# Adafruit_EZ-SFX_with_Headphone.net
KiCad netlist of a schematic drawn in EAGLE
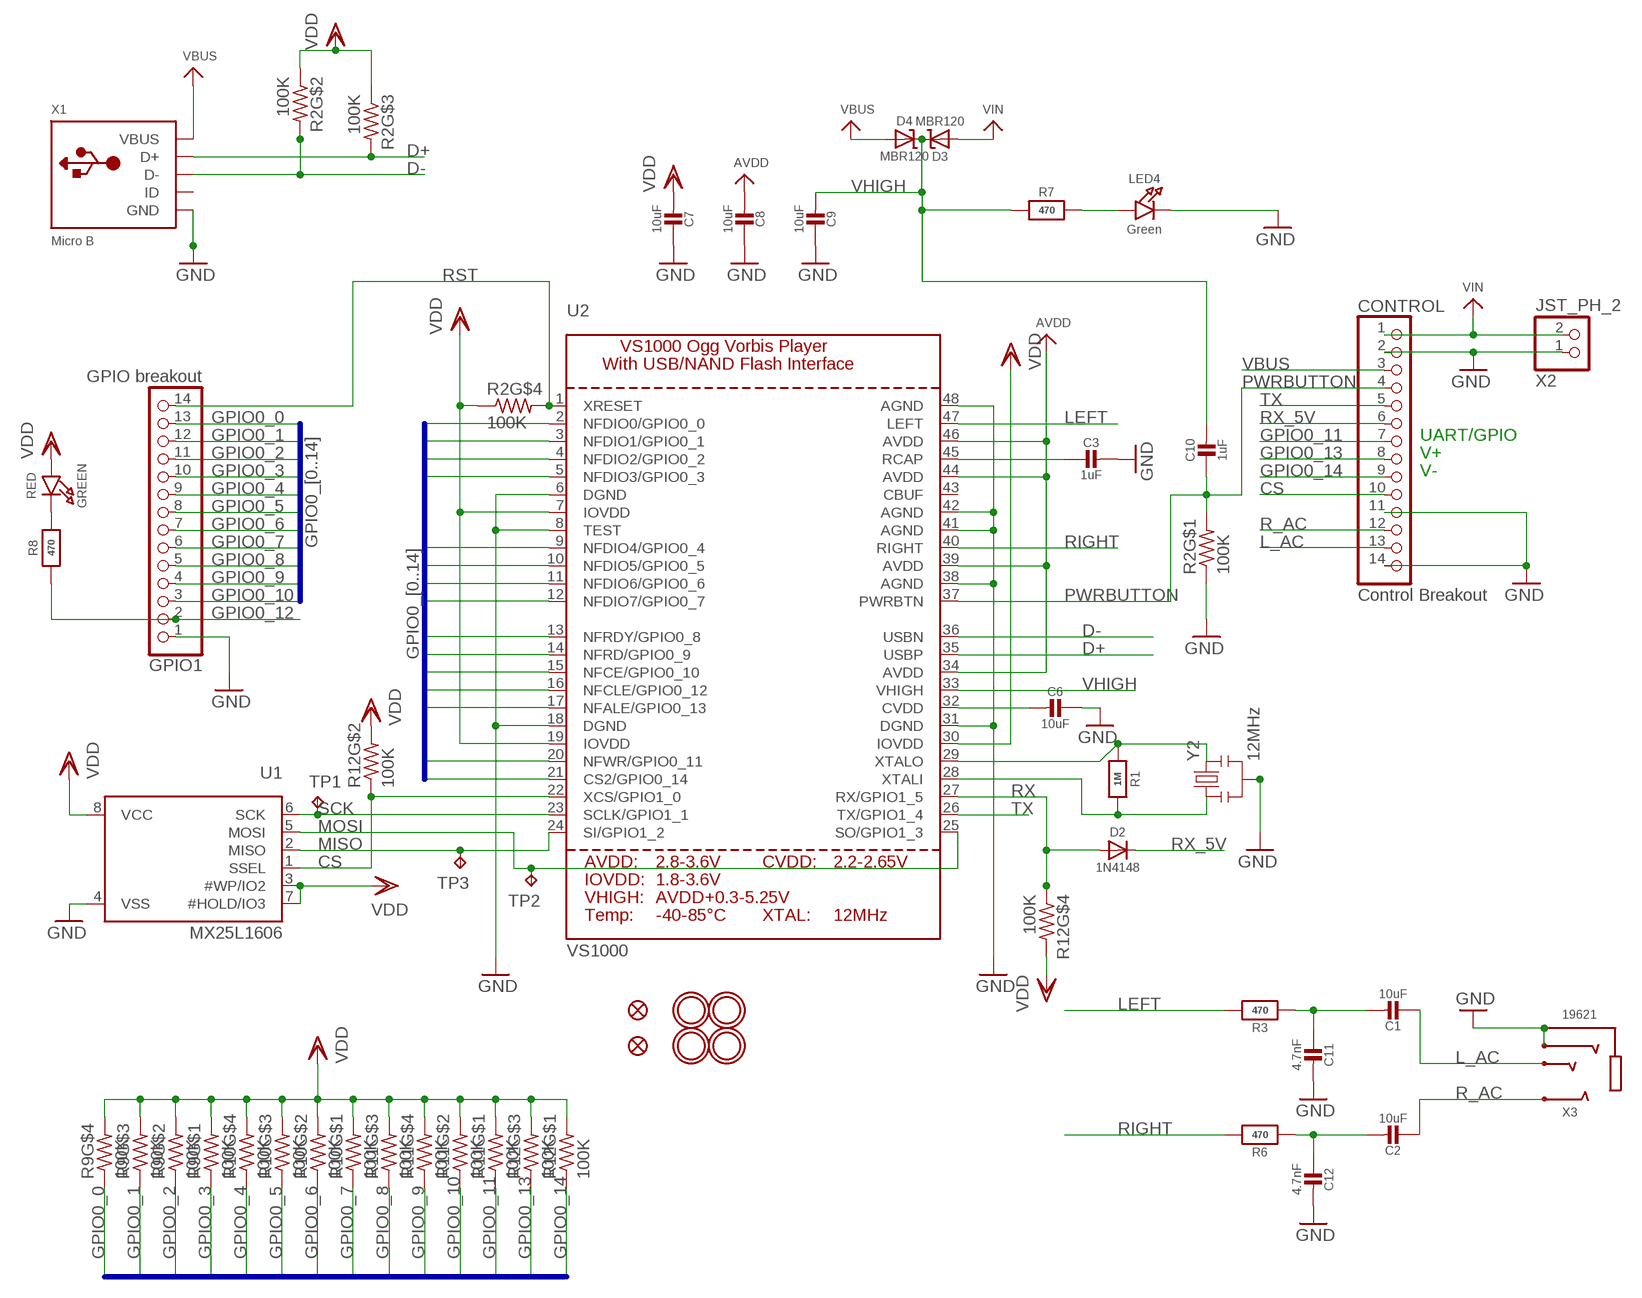
[diagram p0: schematic, sheet 1]

(export (version "E")
  (design (tool "Eeschema 10.0.6"))
  (components
    (comp (ref "C1")
      (value "10uF")
      (footprint "eagle-import:0805-NO")
      (libsource (lib "eagle-import") (part "CAP_CERAMIC0805-NOOUTLINE"))
    )
    (comp (ref "C2")
      (value "10uF")
      (footprint "eagle-import:0805-NO")
      (libsource (lib "eagle-import") (part "CAP_CERAMIC0805-NOOUTLINE"))
    )
    (comp (ref "C3")
      (value "1uF")
      (footprint "eagle-import:0805-NO")
      (libsource (lib "eagle-import") (part "CAP_CERAMIC0805-NOOUTLINE"))
    )
    (comp (ref "C6")
      (value "10uF")
      (footprint "eagle-import:0805_10MGAP")
      (libsource (lib "eagle-import") (part "CAP_CERAMIC0805_10MGAP"))
    )
    (comp (ref "C7")
      (value "10uF")
      (footprint "eagle-import:0805_10MGAP")
      (libsource (lib "eagle-import") (part "CAP_CERAMIC0805_10MGAP"))
    )
    (comp (ref "C8")
      (value "10uF")
      (footprint "eagle-import:0805-NO")
      (libsource (lib "eagle-import") (part "CAP_CERAMIC0805-NOOUTLINE"))
    )
    (comp (ref "C9")
      (value "10uF")
      (footprint "eagle-import:0805-NO")
      (libsource (lib "eagle-import") (part "CAP_CERAMIC0805-NOOUTLINE"))
    )
    (comp (ref "C10")
      (value "1uF")
      (footprint "eagle-import:0805-NO")
      (libsource (lib "eagle-import") (part "CAP_CERAMIC0805-NOOUTLINE"))
    )
    (comp (ref "C11")
      (value "4.7nF")
      (footprint "eagle-import:0805-NO")
      (libsource (lib "eagle-import") (part "CAP_CERAMIC0805-NOOUTLINE"))
    )
    (comp (ref "C12")
      (value "4.7nF")
      (footprint "eagle-import:0805-NO")
      (libsource (lib "eagle-import") (part "CAP_CERAMIC0805-NOOUTLINE"))
    )
    (comp (ref "CONTROL")
      (value "Control Breakout")
      (footprint "eagle-import:1X14-CB")
      (libsource (lib "eagle-import") (part "PINHD-1X14-CB"))
    )
    (comp (ref "D2")
      (value "1N4148")
      (footprint "eagle-import:SOD-323")
      (libsource (lib "eagle-import") (part "DIODESOD-323"))
    )
    (comp (ref "D3")
      (value "MBR120")
      (footprint "eagle-import:SOD-123")
      (libsource (lib "eagle-import") (part "DIODE-SCHOTTKYSOD-123"))
    )
    (comp (ref "D4")
      (value "MBR120")
      (footprint "eagle-import:SOD-123")
      (libsource (lib "eagle-import") (part "DIODE-SCHOTTKYSOD-123"))
    )
    (comp (ref "FID1")
      (value "FIDUCIAL\"\"")
      (footprint "eagle-import:FIDUCIAL_1MM")
      (libsource (lib "eagle-import") (part "FIDUCIAL{dblquote}{dblquote}"))
    )
    (comp (ref "FID2")
      (value "FIDUCIAL\"\"")
      (footprint "eagle-import:FIDUCIAL_1MM")
      (libsource (lib "eagle-import") (part "FIDUCIAL{dblquote}{dblquote}"))
    )
    (comp (ref "GPIO1")
      (value "GPIO breakout")
      (footprint "eagle-import:1X14-CB")
      (libsource (lib "eagle-import") (part "PINHD-1X14-CB"))
    )
    (comp (ref "GREEN")
      (value "RED")
      (footprint "eagle-import:CHIPLED_0805_NOOUTLINE")
      (libsource (lib "eagle-import") (part "LED0805_NOOUTLINE"))
    )
    (comp (ref "LED4")
      (value "Green")
      (footprint "eagle-import:CHIPLED_0805_NOOUTLINE")
      (libsource (lib "eagle-import") (part "LED0805_NOOUTLINE"))
    )
    (comp (ref "R1")
      (value "1M")
      (footprint "eagle-import:0805-NO")
      (libsource (lib "eagle-import") (part "RESISTOR0805_NOOUTLINE"))
    )
    (comp (ref "R2")
      (value "100K")
      (footprint "eagle-import:RESPACK_4X0603")
      (libsource (lib "eagle-import") (part "RESISTOR_4PACK_US"))
    )
    (comp (ref "R3")
      (value "470")
      (footprint "eagle-import:0805-NO")
      (libsource (lib "eagle-import") (part "RESISTOR0805_NOOUTLINE"))
    )
    (comp (ref "R6")
      (value "470")
      (footprint "eagle-import:0805-NO")
      (libsource (lib "eagle-import") (part "RESISTOR0805_NOOUTLINE"))
    )
    (comp (ref "R7")
      (value "470")
      (footprint "eagle-import:0805-NO")
      (libsource (lib "eagle-import") (part "RESISTOR0805_NOOUTLINE"))
    )
    (comp (ref "R8")
      (value "470")
      (footprint "eagle-import:0805-NO")
      (libsource (lib "eagle-import") (part "RESISTOR0805_NOOUTLINE"))
    )
    (comp (ref "R9")
      (value "100K")
      (footprint "eagle-import:RESPACK_4X0603")
      (libsource (lib "eagle-import") (part "RESISTOR_4PACK_US"))
    )
    (comp (ref "R10")
      (value "100K")
      (footprint "eagle-import:RESPACK_4X0603")
      (libsource (lib "eagle-import") (part "RESISTOR_4PACK_US"))
    )
    (comp (ref "R11")
      (value "100K")
      (footprint "eagle-import:RESPACK_4X0603")
      (libsource (lib "eagle-import") (part "RESISTOR_4PACK_US"))
    )
    (comp (ref "R12")
      (value "100K")
      (footprint "eagle-import:RESPACK_4X0603")
      (libsource (lib "eagle-import") (part "RESISTOR_4PACK_US"))
    )
    (comp (ref "TP1")
      (value "TPB1,27")
      (footprint "eagle-import:B1,27")
      (libsource (lib "eagle-import") (part "TPB1,27"))
    )
    (comp (ref "TP2")
      (value "TPB1,27")
      (footprint "eagle-import:B1,27")
      (libsource (lib "eagle-import") (part "TPB1,27"))
    )
    (comp (ref "TP3")
      (value "TPB1,27")
      (footprint "eagle-import:B1,27")
      (libsource (lib "eagle-import") (part "TPB1,27"))
    )
    (comp (ref "U$5")
      (value "MOUNTINGHOLE2.5")
      (footprint "eagle-import:MOUNTINGHOLE_2.5_PLATED")
      (libsource (lib "eagle-import") (part "MOUNTINGHOLE2.5"))
    )
    (comp (ref "U$6")
      (value "MOUNTINGHOLE2.5")
      (footprint "eagle-import:MOUNTINGHOLE_2.5_PLATED")
      (libsource (lib "eagle-import") (part "MOUNTINGHOLE2.5"))
    )
    (comp (ref "U$7")
      (value "MOUNTINGHOLE2.5")
      (footprint "eagle-import:MOUNTINGHOLE_2.5_PLATED")
      (libsource (lib "eagle-import") (part "MOUNTINGHOLE2.5"))
    )
    (comp (ref "U$8")
      (value "MOUNTINGHOLE2.5")
      (footprint "eagle-import:MOUNTINGHOLE_2.5_PLATED")
      (libsource (lib "eagle-import") (part "MOUNTINGHOLE2.5"))
    )
    (comp (ref "U1")
      (value "MX25L1606")
      (footprint "eagle-import:SOIC8_208MIL")
      (libsource (lib "eagle-import") (part "SPIFLASH_SOIC8208MIL"))
    )
    (comp (ref "U2")
      (value "VS1000")
      (footprint "eagle-import:LQFP48")
      (libsource (lib "eagle-import") (part "VS1000"))
    )
    (comp (ref "X1")
      (value "Micro B")
      (footprint "eagle-import:4UCONN_20329")
      (libsource (lib "eagle-import") (part "USBMICRO_20329"))
    )
    (comp (ref "X2")
      (value "JST_PH_2")
      (footprint "eagle-import:JSTPH2")
      (libsource (lib "eagle-import") (part "CON_JST_PH_2PIN"))
    )
    (comp (ref "X3")
      (value "19621")
      (footprint "eagle-import:4UCONN_18510")
      (libsource (lib "eagle-import") (part "AUDIO_3.5MMJACK_4POL"))
    )
    (comp (ref "Y2")
      (value "12MHz")
      (footprint "eagle-import:RESONATOR-SMD")
      (libsource (lib "eagle-import") (part "RESONATORSMD"))
    )
  )
  (nets
    (net (code "1") (name "/CS") (class "Default")
      (node (ref "CONTROL") (pin "10") (pinfunction "10_10") (pintype "passive"))
      (node (ref "R12") (pin "2") (pinfunction "1_2") (pintype "passive"))
      (node (ref "U1") (pin "1") (pinfunction "SSEL_1") (pintype "bidirectional"))
      (node (ref "U2") (pin "22") (pinfunction "XCS/GPIO1_0_22") (pintype "bidirectional"))
    )
    (net (code "2") (name "/D+") (class "Default")
      (node (ref "R2") (pin "6") (pinfunction "2_6") (pintype "passive"))
      (node (ref "U2") (pin "35") (pinfunction "USBP_35") (pintype "bidirectional"))
      (node (ref "X1") (pin "D+") (pinfunction "D+_D+") (pintype "bidirectional"))
    )
    (net (code "3") (name "/D-") (class "Default")
      (node (ref "R2") (pin "7") (pinfunction "2_7") (pintype "passive"))
      (node (ref "U2") (pin "36") (pinfunction "USBN_36") (pintype "bidirectional"))
      (node (ref "X1") (pin "D-") (pinfunction "D-_D-") (pintype "bidirectional"))
    )
    (net (code "4") (name "/GPIO0_0") (class "Default")
      (node (ref "GPIO1") (pin "13") (pinfunction "13_13") (pintype "passive"))
      (node (ref "R9") (pin "4") (pinfunction "1_4") (pintype "passive"))
      (node (ref "U2") (pin "2") (pinfunction "NFDIO0/GPIO0_0_2") (pintype "bidirectional"))
    )
    (net (code "5") (name "/GPIO0_1") (class "Default")
      (node (ref "GPIO1") (pin "12") (pinfunction "12_12") (pintype "passive"))
      (node (ref "R9") (pin "3") (pinfunction "1_3") (pintype "passive"))
      (node (ref "U2") (pin "3") (pinfunction "NFDIO1/GPIO0_1_3") (pintype "bidirectional"))
    )
    (net (code "6") (name "/GPIO0_2") (class "Default")
      (node (ref "GPIO1") (pin "11") (pinfunction "11_11") (pintype "passive"))
      (node (ref "R9") (pin "2") (pinfunction "1_2") (pintype "passive"))
      (node (ref "U2") (pin "4") (pinfunction "NFDIO2/GPIO0_2_4") (pintype "bidirectional"))
    )
    (net (code "7") (name "/GPIO0_3") (class "Default")
      (node (ref "GPIO1") (pin "10") (pinfunction "10_10") (pintype "passive"))
      (node (ref "R9") (pin "1") (pinfunction "1_1") (pintype "passive"))
      (node (ref "U2") (pin "5") (pinfunction "NFDIO3/GPIO0_3_5") (pintype "bidirectional"))
    )
    (net (code "8") (name "/GPIO0_4") (class "Default")
      (node (ref "GPIO1") (pin "9") (pinfunction "9_9") (pintype "passive"))
      (node (ref "R10") (pin "4") (pinfunction "1_4") (pintype "passive"))
      (node (ref "U2") (pin "9") (pinfunction "NFDIO4/GPIO0_4_9") (pintype "bidirectional"))
    )
    (net (code "9") (name "/GPIO0_5") (class "Default")
      (node (ref "GPIO1") (pin "8") (pinfunction "8_8") (pintype "passive"))
      (node (ref "R10") (pin "3") (pinfunction "1_3") (pintype "passive"))
      (node (ref "U2") (pin "10") (pinfunction "NFDIO5/GPIO0_5_10") (pintype "bidirectional"))
    )
    (net (code "10") (name "/GPIO0_6") (class "Default")
      (node (ref "GPIO1") (pin "7") (pinfunction "7_7") (pintype "passive"))
      (node (ref "R10") (pin "2") (pinfunction "1_2") (pintype "passive"))
      (node (ref "U2") (pin "11") (pinfunction "NFDIO6/GPIO0_6_11") (pintype "bidirectional"))
    )
    (net (code "11") (name "/GPIO0_7") (class "Default")
      (node (ref "GPIO1") (pin "6") (pinfunction "6_6") (pintype "passive"))
      (node (ref "R10") (pin "1") (pinfunction "1_1") (pintype "passive"))
      (node (ref "U2") (pin "12") (pinfunction "NFDIO7/GPIO0_7_12") (pintype "bidirectional"))
    )
    (net (code "12") (name "/GPIO0_8") (class "Default")
      (node (ref "GPIO1") (pin "5") (pinfunction "5_5") (pintype "passive"))
      (node (ref "R11") (pin "3") (pinfunction "1_3") (pintype "passive"))
      (node (ref "U2") (pin "13") (pinfunction "NFRDY/GPIO0_8_13") (pintype "bidirectional"))
    )
    (net (code "13") (name "/GPIO0_9") (class "Default")
      (node (ref "GPIO1") (pin "4") (pinfunction "4_4") (pintype "passive"))
      (node (ref "R11") (pin "4") (pinfunction "1_4") (pintype "passive"))
      (node (ref "U2") (pin "14") (pinfunction "NFRD/GPIO0_9_14") (pintype "bidirectional"))
    )
    (net (code "14") (name "/GPIO0_10") (class "Default")
      (node (ref "GPIO1") (pin "3") (pinfunction "3_3") (pintype "passive"))
      (node (ref "R11") (pin "2") (pinfunction "1_2") (pintype "passive"))
      (node (ref "U2") (pin "15") (pinfunction "NFCE/GPIO0_10_15") (pintype "bidirectional"))
    )
    (net (code "15") (name "/GPIO0_11") (class "Default")
      (node (ref "CONTROL") (pin "7") (pinfunction "7_7") (pintype "passive"))
      (node (ref "R11") (pin "1") (pinfunction "1_1") (pintype "passive"))
      (node (ref "U2") (pin "20") (pinfunction "NFWR/GPIO0_11_20") (pintype "bidirectional"))
    )
    (net (code "16") (name "/GPIO0_12") (class "Default")
      (node (ref "GPIO1") (pin "2") (pinfunction "2_2") (pintype "passive"))
      (node (ref "R8") (pin "2") (pinfunction "2_2") (pintype "passive"))
      (node (ref "U2") (pin "16") (pinfunction "NFCLE/GPIO0_12_16") (pintype "bidirectional"))
    )
    (net (code "17") (name "/GPIO0_13") (class "Default")
      (node (ref "CONTROL") (pin "8") (pinfunction "8_8") (pintype "passive"))
      (node (ref "R12") (pin "3") (pinfunction "1_3") (pintype "passive"))
      (node (ref "U2") (pin "17") (pinfunction "NFALE/GPIO0_13_17") (pintype "bidirectional"))
    )
    (net (code "18") (name "/GPIO0_14") (class "Default")
      (node (ref "CONTROL") (pin "9") (pinfunction "9_9") (pintype "passive"))
      (node (ref "R12") (pin "1") (pinfunction "1_1") (pintype "passive"))
      (node (ref "U2") (pin "21") (pinfunction "CS2/GPIO0_14_21") (pintype "bidirectional"))
    )
    (net (code "20") (name "/LEFT") (class "Default")
      (node (ref "R3") (pin "1") (pinfunction "1_1") (pintype "passive"))
      (node (ref "U2") (pin "47") (pinfunction "LEFT_47") (pintype "bidirectional"))
    )
    (net (code "21") (name "/L_AC") (class "Default")
      (node (ref "C1") (pin "1") (pinfunction "1_1") (pintype "passive"))
      (node (ref "CONTROL") (pin "13") (pinfunction "13_13") (pintype "passive"))
      (node (ref "X3") (pin "2-TIP") (pinfunction "RING3_2-TIP") (pintype "passive"))
    )
    (net (code "22") (name "/MISO") (class "Default")
      (node (ref "TP3") (pin "TP") (pinfunction "TP_TP") (pintype "input"))
      (node (ref "U1") (pin "2") (pinfunction "MISO_2") (pintype "bidirectional"))
      (node (ref "U2") (pin "24") (pinfunction "SI/GPIO1_2_24") (pintype "bidirectional"))
    )
    (net (code "23") (name "/MOSI") (class "Default")
      (node (ref "TP2") (pin "TP") (pinfunction "TP_TP") (pintype "input"))
      (node (ref "U1") (pin "5") (pinfunction "MOSI_5") (pintype "bidirectional"))
      (node (ref "U2") (pin "25") (pinfunction "SO/GPIO1_3_25") (pintype "bidirectional"))
    )
    (net (code "24") (name "/PWRBUTTON") (class "Default")
      (node (ref "C10") (pin "1") (pinfunction "1_1") (pintype "passive"))
      (node (ref "CONTROL") (pin "4") (pinfunction "4_4") (pintype "passive"))
      (node (ref "R2") (pin "8") (pinfunction "2_8") (pintype "passive"))
      (node (ref "U2") (pin "37") (pinfunction "PWRBTN_37") (pintype "bidirectional"))
    )
    (net (code "25") (name "/RIGHT") (class "Default")
      (node (ref "R6") (pin "1") (pinfunction "1_1") (pintype "passive"))
      (node (ref "U2") (pin "40") (pinfunction "RIGHT_40") (pintype "bidirectional"))
    )
    (net (code "26") (name "/RST") (class "Default")
      (node (ref "GPIO1") (pin "14") (pinfunction "14_14") (pintype "passive"))
      (node (ref "R2") (pin "5") (pinfunction "2_5") (pintype "passive"))
      (node (ref "U2") (pin "1") (pinfunction "XRESET_1") (pintype "bidirectional"))
    )
    (net (code "27") (name "/RX") (class "Default")
      (node (ref "D2") (pin "A") (pinfunction "A_A") (pintype "passive"))
      (node (ref "R12") (pin "4") (pinfunction "1_4") (pintype "passive"))
      (node (ref "U2") (pin "27") (pinfunction "RX/GPIO1_5_27") (pintype "bidirectional"))
    )
    (net (code "28") (name "/RX_5V") (class "Default")
      (node (ref "CONTROL") (pin "6") (pinfunction "6_6") (pintype "passive"))
      (node (ref "D2") (pin "C") (pinfunction "C_C") (pintype "passive"))
    )
    (net (code "29") (name "/R_AC") (class "Default")
      (node (ref "C2") (pin "1") (pinfunction "1_1") (pintype "passive"))
      (node (ref "CONTROL") (pin "12") (pinfunction "12_12") (pintype "passive"))
      (node (ref "X3") (pin "3-OUTER_SLEEVE") (pinfunction "RING2_3-OUTER_SLEEVE") (pintype "passive"))
    )
    (net (code "30") (name "/SCK") (class "Default")
      (node (ref "TP1") (pin "TP") (pinfunction "TP_TP") (pintype "input"))
      (node (ref "U1") (pin "6") (pinfunction "SCK_6") (pintype "bidirectional"))
      (node (ref "U2") (pin "23") (pinfunction "SCLK/GPIO1_1_23") (pintype "bidirectional"))
    )
    (net (code "31") (name "/TX") (class "Default")
      (node (ref "CONTROL") (pin "5") (pinfunction "5_5") (pintype "passive"))
      (node (ref "U2") (pin "26") (pinfunction "TX/GPIO1_4_26") (pintype "bidirectional"))
    )
    (net (code "32") (name "/VHIGH") (class "Default")
      (node (ref "C10") (pin "2") (pinfunction "2_2") (pintype "passive"))
      (node (ref "C9") (pin "2") (pinfunction "2_2") (pintype "passive"))
      (node (ref "D3") (pin "C") (pinfunction "C_C") (pintype "passive"))
      (node (ref "D4") (pin "C") (pinfunction "C_C") (pintype "passive"))
      (node (ref "R7") (pin "2") (pinfunction "2_2") (pintype "passive"))
      (node (ref "U2") (pin "33") (pinfunction "VHIGH_33") (pintype "power_in"))
    )
    (net (code "33") (name "AVDD") (class "Default")
      (node (ref "C8") (pin "2") (pinfunction "2_2") (pintype "passive"))
      (node (ref "U2") (pin "34") (pinfunction "AVDD_34") (pintype "power_in"))
      (node (ref "U2") (pin "39") (pinfunction "AVDD_39") (pintype "power_in"))
      (node (ref "U2") (pin "44") (pinfunction "AVDD_44") (pintype "power_in"))
      (node (ref "U2") (pin "46") (pinfunction "AVDD_46") (pintype "power_in"))
    )
    (net (code "34") (name "GND") (class "Default")
      (node (ref "C11") (pin "2") (pinfunction "2_2") (pintype "passive"))
      (node (ref "C12") (pin "2") (pinfunction "2_2") (pintype "passive"))
      (node (ref "C3") (pin "2") (pinfunction "2_2") (pintype "passive"))
      (node (ref "C6") (pin "1") (pinfunction "1_1") (pintype "passive"))
      (node (ref "C7") (pin "1") (pinfunction "1_1") (pintype "passive"))
      (node (ref "C8") (pin "1") (pinfunction "1_1") (pintype "passive"))
      (node (ref "C9") (pin "1") (pinfunction "1_1") (pintype "passive"))
      (node (ref "CONTROL") (pin "11") (pinfunction "11_11") (pintype "passive"))
      (node (ref "CONTROL") (pin "14") (pinfunction "14_14") (pintype "passive"))
      (node (ref "CONTROL") (pin "2") (pinfunction "2_2") (pintype "passive"))
      (node (ref "GPIO1") (pin "1") (pinfunction "1_1") (pintype "passive"))
      (node (ref "LED4") (pin "C") (pinfunction "C_C") (pintype "passive"))
      (node (ref "R2") (pin "1") (pinfunction "1_1") (pintype "passive"))
      (node (ref "U1") (pin "4") (pinfunction "VSS_4") (pintype "bidirectional"))
      (node (ref "U2") (pin "18") (pinfunction "DGND_18") (pintype "power_in"))
      (node (ref "U2") (pin "31") (pinfunction "DGND_31") (pintype "power_in"))
      (node (ref "U2") (pin "38") (pinfunction "AGND_38") (pintype "power_in"))
      (node (ref "U2") (pin "41") (pinfunction "AGND_41") (pintype "power_in"))
      (node (ref "U2") (pin "42") (pinfunction "AGND_42") (pintype "power_in"))
      (node (ref "U2") (pin "48") (pinfunction "AGND_48") (pintype "power_in"))
      (node (ref "U2") (pin "6") (pinfunction "DGND_6") (pintype "power_in"))
      (node (ref "U2") (pin "8") (pinfunction "TEST_8") (pintype "bidirectional"))
      (node (ref "X1") (pin "BASE@1") (pinfunction "GND_BASE@1") (pintype "power_in"))
      (node (ref "X1") (pin "BASE@2") (pinfunction "GND_BASE@2") (pintype "power_in"))
      (node (ref "X1") (pin "GND") (pinfunction "GND_GND") (pintype "power_in"))
      (node (ref "X1") (pin "SPRT@1") (pinfunction "GND_SPRT@1") (pintype "power_in"))
      (node (ref "X1") (pin "SPRT@2") (pinfunction "GND_SPRT@2") (pintype "power_in"))
      (node (ref "X1") (pin "SPRT@3") (pinfunction "GND_SPRT@3") (pintype "power_in"))
      (node (ref "X1") (pin "SPRT@4") (pinfunction "GND_SPRT@4") (pintype "power_in"))
      (node (ref "X2") (pin "1") (pinfunction "1_1") (pintype "passive"))
      (node (ref "X3") (pin "1-GND") (pinfunction "TIP_1-GND") (pintype "passive"))
      (node (ref "X3") (pin "4-INNER_SLEEVE") (pinfunction "RING1_4-INNER_SLEEVE") (pintype "passive"))
      (node (ref "Y2") (pin "2") (pinfunction "2_2") (pintype "passive"))
    )
    (net (code "35") (name "Net-(C1-Pad2)") (class "Default")
      (node (ref "C1") (pin "2") (pinfunction "2_2") (pintype "passive"))
      (node (ref "C11") (pin "1") (pinfunction "1_1") (pintype "passive"))
      (node (ref "R3") (pin "2") (pinfunction "2_2") (pintype "passive"))
    )
    (net (code "36") (name "Net-(C12-Pad1)") (class "Default")
      (node (ref "C12") (pin "1") (pinfunction "1_1") (pintype "passive"))
      (node (ref "C2") (pin "2") (pinfunction "2_2") (pintype "passive"))
      (node (ref "R6") (pin "2") (pinfunction "2_2") (pintype "passive"))
    )
    (net (code "37") (name "Net-(GREEN-PadC)") (class "Default")
      (node (ref "GREEN") (pin "C") (pinfunction "C_C") (pintype "passive"))
      (node (ref "R8") (pin "1") (pinfunction "1_1") (pintype "passive"))
    )
    (net (code "38") (name "Net-(LED4-PadA)") (class "Default")
      (node (ref "LED4") (pin "A") (pinfunction "A_A") (pintype "passive"))
      (node (ref "R7") (pin "1") (pinfunction "1_1") (pintype "passive"))
    )
    (net (code "39") (name "Net-(U2-CVDD)") (class "Default")
      (node (ref "C6") (pin "2") (pinfunction "2_2") (pintype "passive"))
      (node (ref "U2") (pin "32") (pinfunction "CVDD_32") (pintype "power_in"))
    )
    (net (code "40") (name "Net-(U2-RCAP)") (class "Default")
      (node (ref "C3") (pin "1") (pinfunction "1_1") (pintype "passive"))
      (node (ref "U2") (pin "45") (pinfunction "RCAP_45") (pintype "bidirectional"))
    )
    (net (code "41") (name "Net-(U2-XTALI)") (class "Default")
      (node (ref "R1") (pin "1") (pinfunction "1_1") (pintype "passive"))
      (node (ref "U2") (pin "28") (pinfunction "XTALI_28") (pintype "bidirectional"))
      (node (ref "Y2") (pin "1") (pinfunction "1_1") (pintype "passive"))
    )
    (net (code "42") (name "Net-(U2-XTALO)") (class "Default")
      (node (ref "R1") (pin "2") (pinfunction "2_2") (pintype "passive"))
      (node (ref "U2") (pin "29") (pinfunction "XTALO_29") (pintype "bidirectional"))
      (node (ref "Y2") (pin "3") (pinfunction "3_3") (pintype "passive"))
    )
    (net (code "43") (name "VBUS") (class "Default")
      (node (ref "CONTROL") (pin "3") (pinfunction "3_3") (pintype "passive"))
      (node (ref "D4") (pin "A") (pinfunction "A_A") (pintype "passive"))
      (node (ref "X1") (pin "VBUS") (pinfunction "VBUS_VBUS") (pintype "power_in"))
    )
    (net (code "44") (name "VDD") (class "Default")
      (node (ref "C7") (pin "2") (pinfunction "2_2") (pintype "passive"))
      (node (ref "GREEN") (pin "A") (pinfunction "A_A") (pintype "passive"))
      (node (ref "R10") (pin "5") (pinfunction "2_5") (pintype "passive"))
      (node (ref "R10") (pin "6") (pinfunction "2_6") (pintype "passive"))
      (node (ref "R10") (pin "7") (pinfunction "2_7") (pintype "passive"))
      (node (ref "R10") (pin "8") (pinfunction "2_8") (pintype "passive"))
      (node (ref "R11") (pin "5") (pinfunction "2_5") (pintype "passive"))
      (node (ref "R11") (pin "6") (pinfunction "2_6") (pintype "passive"))
      (node (ref "R11") (pin "7") (pinfunction "2_7") (pintype "passive"))
      (node (ref "R11") (pin "8") (pinfunction "2_8") (pintype "passive"))
      (node (ref "R12") (pin "5") (pinfunction "2_5") (pintype "passive"))
      (node (ref "R12") (pin "6") (pinfunction "2_6") (pintype "passive"))
      (node (ref "R12") (pin "7") (pinfunction "2_7") (pintype "passive"))
      (node (ref "R12") (pin "8") (pinfunction "2_8") (pintype "passive"))
      (node (ref "R2") (pin "2") (pinfunction "1_2") (pintype "passive"))
      (node (ref "R2") (pin "3") (pinfunction "1_3") (pintype "passive"))
      (node (ref "R2") (pin "4") (pinfunction "1_4") (pintype "passive"))
      (node (ref "R9") (pin "5") (pinfunction "2_5") (pintype "passive"))
      (node (ref "R9") (pin "6") (pinfunction "2_6") (pintype "passive"))
      (node (ref "R9") (pin "7") (pinfunction "2_7") (pintype "passive"))
      (node (ref "R9") (pin "8") (pinfunction "2_8") (pintype "passive"))
      (node (ref "U1") (pin "3") (pinfunction "#WP/IO2_3") (pintype "bidirectional"))
      (node (ref "U1") (pin "7") (pinfunction "#HOLD/IO3_7") (pintype "bidirectional"))
      (node (ref "U1") (pin "8") (pinfunction "VCC_8") (pintype "bidirectional"))
      (node (ref "U2") (pin "19") (pinfunction "IOVDD_19") (pintype "power_in"))
      (node (ref "U2") (pin "30") (pinfunction "IOVDD_30") (pintype "power_in"))
      (node (ref "U2") (pin "7") (pinfunction "IOVDD_7") (pintype "power_in"))
    )
    (net (code "45") (name "VIN") (class "Default")
      (node (ref "CONTROL") (pin "1") (pinfunction "1_1") (pintype "passive"))
      (node (ref "D3") (pin "A") (pinfunction "A_A") (pintype "passive"))
      (node (ref "X2") (pin "2") (pinfunction "2_2") (pintype "passive"))
    )
    (net (code "46") (name "unconnected-(U2-CBUF-Pad43)") (class "Default")
      (node (ref "U2") (pin "43") (pinfunction "CBUF_43") (pintype "bidirectional"))
    )
    (net (code "47") (name "unconnected-(X1-PadID)") (class "Default")
      (node (ref "X1") (pin "ID") (pinfunction "ID_ID") (pintype "bidirectional"))
    )
  )
)
